# atmega328_breakout.net
KiCad netlist of a schematic drawn in EAGLE
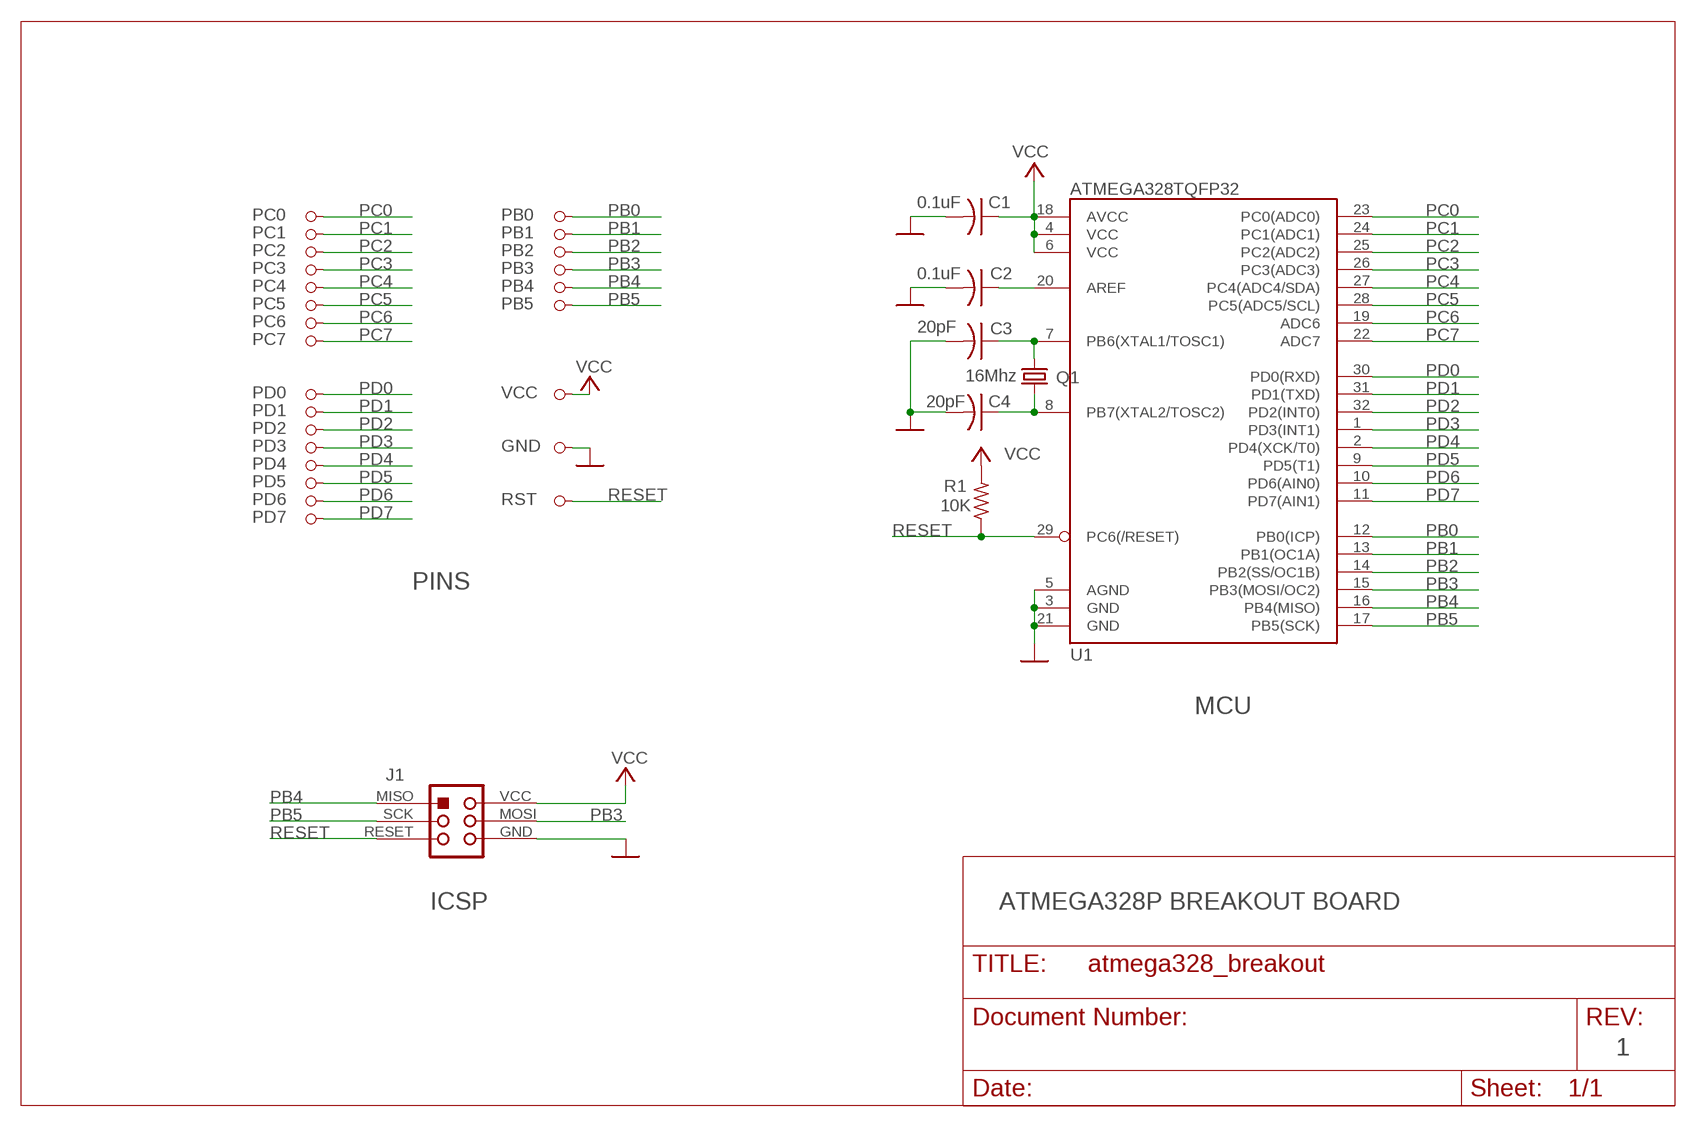
[diagram p0: schematic, sheet 1]

(export (version "E")
  (design (tool "Eeschema 10.0.6"))
  (components
    (comp (ref "C1")
      (value "0.1uF")
      (footprint "eagle-import:C0603")
      (libsource (lib "eagle-import") (part "CAP-C0603"))
    )
    (comp (ref "C2")
      (value "0.1uF")
      (footprint "eagle-import:C0603")
      (libsource (lib "eagle-import") (part "CAP-C0603"))
    )
    (comp (ref "C3")
      (value "20pF")
      (footprint "eagle-import:C0603")
      (libsource (lib "eagle-import") (part "CAP-C0603"))
    )
    (comp (ref "C4")
      (value "20pF")
      (footprint "eagle-import:C0603")
      (libsource (lib "eagle-import") (part "CAP-C0603"))
    )
    (comp (ref "GND")
      (value "PINHD-1X1")
      (footprint "eagle-import:1X01")
      (libsource (lib "eagle-import") (part "PINHD-1X1"))
    )
    (comp (ref "J1")
      (value "ICSP")
      (footprint "eagle-import:ICSP")
      (libsource (lib "eagle-import") (part "ICSP"))
    )
    (comp (ref "PB0")
      (value "PINHD-1X1")
      (footprint "eagle-import:1X01")
      (libsource (lib "eagle-import") (part "PINHD-1X1"))
    )
    (comp (ref "PB1")
      (value "PINHD-1X1")
      (footprint "eagle-import:1X01")
      (libsource (lib "eagle-import") (part "PINHD-1X1"))
    )
    (comp (ref "PB2")
      (value "PINHD-1X1")
      (footprint "eagle-import:1X01")
      (libsource (lib "eagle-import") (part "PINHD-1X1"))
    )
    (comp (ref "PB3")
      (value "PINHD-1X1")
      (footprint "eagle-import:1X01")
      (libsource (lib "eagle-import") (part "PINHD-1X1"))
    )
    (comp (ref "PB4")
      (value "PINHD-1X1")
      (footprint "eagle-import:1X01")
      (libsource (lib "eagle-import") (part "PINHD-1X1"))
    )
    (comp (ref "PB5")
      (value "PINHD-1X1")
      (footprint "eagle-import:1X01")
      (libsource (lib "eagle-import") (part "PINHD-1X1"))
    )
    (comp (ref "PC0")
      (value "PINHD-1X1")
      (footprint "eagle-import:1X01")
      (libsource (lib "eagle-import") (part "PINHD-1X1"))
    )
    (comp (ref "PC1")
      (value "PINHD-1X1")
      (footprint "eagle-import:1X01")
      (libsource (lib "eagle-import") (part "PINHD-1X1"))
    )
    (comp (ref "PC2")
      (value "PINHD-1X1")
      (footprint "eagle-import:1X01")
      (libsource (lib "eagle-import") (part "PINHD-1X1"))
    )
    (comp (ref "PC3")
      (value "PINHD-1X1")
      (footprint "eagle-import:1X01")
      (libsource (lib "eagle-import") (part "PINHD-1X1"))
    )
    (comp (ref "PC4")
      (value "PINHD-1X1")
      (footprint "eagle-import:1X01")
      (libsource (lib "eagle-import") (part "PINHD-1X1"))
    )
    (comp (ref "PC5")
      (value "PINHD-1X1")
      (footprint "eagle-import:1X01")
      (libsource (lib "eagle-import") (part "PINHD-1X1"))
    )
    (comp (ref "PC6")
      (value "PINHD-1X1")
      (footprint "eagle-import:1X01")
      (libsource (lib "eagle-import") (part "PINHD-1X1"))
    )
    (comp (ref "PC7")
      (value "PINHD-1X1")
      (footprint "eagle-import:1X01")
      (libsource (lib "eagle-import") (part "PINHD-1X1"))
    )
    (comp (ref "PD0")
      (value "PINHD-1X1")
      (footprint "eagle-import:1X01")
      (libsource (lib "eagle-import") (part "PINHD-1X1"))
    )
    (comp (ref "PD1")
      (value "PINHD-1X1")
      (footprint "eagle-import:1X01")
      (libsource (lib "eagle-import") (part "PINHD-1X1"))
    )
    (comp (ref "PD2")
      (value "PINHD-1X1")
      (footprint "eagle-import:1X01")
      (libsource (lib "eagle-import") (part "PINHD-1X1"))
    )
    (comp (ref "PD3")
      (value "PINHD-1X1")
      (footprint "eagle-import:1X01")
      (libsource (lib "eagle-import") (part "PINHD-1X1"))
    )
    (comp (ref "PD4")
      (value "PINHD-1X1")
      (footprint "eagle-import:1X01")
      (libsource (lib "eagle-import") (part "PINHD-1X1"))
    )
    (comp (ref "PD5")
      (value "PINHD-1X1")
      (footprint "eagle-import:1X01")
      (libsource (lib "eagle-import") (part "PINHD-1X1"))
    )
    (comp (ref "PD6")
      (value "PINHD-1X1")
      (footprint "eagle-import:1X01")
      (libsource (lib "eagle-import") (part "PINHD-1X1"))
    )
    (comp (ref "PD7")
      (value "PINHD-1X1")
      (footprint "eagle-import:1X01")
      (libsource (lib "eagle-import") (part "PINHD-1X1"))
    )
    (comp (ref "Q1")
      (value "16Mhz")
      (footprint "eagle-import:CRYSTAL-CTS406")
      (libsource (lib "eagle-import") (part "CRYSTALCTS406"))
    )
    (comp (ref "R1")
      (value "10K")
      (footprint "eagle-import:R0603")
      (libsource (lib "eagle-import") (part "RES-R0603"))
    )
    (comp (ref "RST")
      (value "PINHD-1X1")
      (footprint "eagle-import:1X01")
      (libsource (lib "eagle-import") (part "PINHD-1X1"))
    )
    (comp (ref "U1")
      (value "ATMEGA328TQFP32")
      (footprint "eagle-import:TQFP32-08")
      (libsource (lib "eagle-import") (part "ATMEGA328TQFP32"))
    )
    (comp (ref "VCC")
      (value "PINHD-1X1")
      (footprint "eagle-import:1X01")
      (libsource (lib "eagle-import") (part "PINHD-1X1"))
    )
  )
  (nets
    (net (code "1") (name "/PB0") (class "Default")
      (node (ref "PB0") (pin "1") (pinfunction "1_1") (pintype "passive"))
      (node (ref "U1") (pin "12") (pinfunction "PB0(ICP)_12") (pintype "bidirectional"))
    )
    (net (code "2") (name "/PB1") (class "Default")
      (node (ref "PB1") (pin "1") (pinfunction "1_1") (pintype "passive"))
      (node (ref "U1") (pin "13") (pinfunction "PB1(OC1A)_13") (pintype "bidirectional"))
    )
    (net (code "3") (name "/PB2") (class "Default")
      (node (ref "PB2") (pin "1") (pinfunction "1_1") (pintype "passive"))
      (node (ref "U1") (pin "14") (pinfunction "PB2(SS/OC1B)_14") (pintype "bidirectional"))
    )
    (net (code "4") (name "/PB3") (class "Default")
      (node (ref "J1") (pin "MOSI") (pinfunction "MOSI_MOSI") (pintype "passive"))
      (node (ref "PB3") (pin "1") (pinfunction "1_1") (pintype "passive"))
      (node (ref "U1") (pin "15") (pinfunction "PB3(MOSI/OC2)_15") (pintype "bidirectional"))
    )
    (net (code "5") (name "/PB4") (class "Default")
      (node (ref "J1") (pin "MISO") (pinfunction "MISO_MISO") (pintype "passive"))
      (node (ref "PB4") (pin "1") (pinfunction "1_1") (pintype "passive"))
      (node (ref "U1") (pin "16") (pinfunction "PB4(MISO)_16") (pintype "bidirectional"))
    )
    (net (code "6") (name "/PB5") (class "Default")
      (node (ref "J1") (pin "SCK") (pinfunction "SCK_SCK") (pintype "passive"))
      (node (ref "PB5") (pin "1") (pinfunction "1_1") (pintype "passive"))
      (node (ref "U1") (pin "17") (pinfunction "PB5(SCK)_17") (pintype "bidirectional"))
    )
    (net (code "7") (name "/PC0") (class "Default")
      (node (ref "PC0") (pin "1") (pinfunction "1_1") (pintype "passive"))
      (node (ref "U1") (pin "23") (pinfunction "PC0(ADC0)_23") (pintype "bidirectional"))
    )
    (net (code "8") (name "/PC1") (class "Default")
      (node (ref "PC1") (pin "1") (pinfunction "1_1") (pintype "passive"))
      (node (ref "U1") (pin "24") (pinfunction "PC1(ADC1)_24") (pintype "bidirectional"))
    )
    (net (code "9") (name "/PC2") (class "Default")
      (node (ref "PC2") (pin "1") (pinfunction "1_1") (pintype "passive"))
      (node (ref "U1") (pin "25") (pinfunction "PC2(ADC2)_25") (pintype "bidirectional"))
    )
    (net (code "10") (name "/PC3") (class "Default")
      (node (ref "PC3") (pin "1") (pinfunction "1_1") (pintype "passive"))
      (node (ref "U1") (pin "26") (pinfunction "PC3(ADC3)_26") (pintype "bidirectional"))
    )
    (net (code "11") (name "/PC4") (class "Default")
      (node (ref "PC4") (pin "1") (pinfunction "1_1") (pintype "passive"))
      (node (ref "U1") (pin "27") (pinfunction "PC4(ADC4/SDA)_27") (pintype "bidirectional"))
    )
    (net (code "12") (name "/PC5") (class "Default")
      (node (ref "PC5") (pin "1") (pinfunction "1_1") (pintype "passive"))
      (node (ref "U1") (pin "28") (pinfunction "PC5(ADC5/SCL)_28") (pintype "bidirectional"))
    )
    (net (code "13") (name "/PC6") (class "Default")
      (node (ref "PC6") (pin "1") (pinfunction "1_1") (pintype "passive"))
      (node (ref "U1") (pin "19") (pinfunction "ADC6_19") (pintype "bidirectional"))
    )
    (net (code "14") (name "/PC7") (class "Default")
      (node (ref "PC7") (pin "1") (pinfunction "1_1") (pintype "passive"))
      (node (ref "U1") (pin "22") (pinfunction "ADC7_22") (pintype "bidirectional"))
    )
    (net (code "15") (name "/PD0") (class "Default")
      (node (ref "PD0") (pin "1") (pinfunction "1_1") (pintype "passive"))
      (node (ref "U1") (pin "30") (pinfunction "PD0(RXD)_30") (pintype "bidirectional"))
    )
    (net (code "16") (name "/PD1") (class "Default")
      (node (ref "PD1") (pin "1") (pinfunction "1_1") (pintype "passive"))
      (node (ref "U1") (pin "31") (pinfunction "PD1(TXD)_31") (pintype "bidirectional"))
    )
    (net (code "17") (name "/PD2") (class "Default")
      (node (ref "PD2") (pin "1") (pinfunction "1_1") (pintype "passive"))
      (node (ref "U1") (pin "32") (pinfunction "PD2(INT0)_32") (pintype "bidirectional"))
    )
    (net (code "18") (name "/PD3") (class "Default")
      (node (ref "PD3") (pin "1") (pinfunction "1_1") (pintype "passive"))
      (node (ref "U1") (pin "1") (pinfunction "PD3(INT1)_1") (pintype "bidirectional"))
    )
    (net (code "19") (name "/PD4") (class "Default")
      (node (ref "PD4") (pin "1") (pinfunction "1_1") (pintype "passive"))
      (node (ref "U1") (pin "2") (pinfunction "PD4(XCK/T0)_2") (pintype "bidirectional"))
    )
    (net (code "20") (name "/PD5") (class "Default")
      (node (ref "PD5") (pin "1") (pinfunction "1_1") (pintype "passive"))
      (node (ref "U1") (pin "9") (pinfunction "PD5(T1)_9") (pintype "bidirectional"))
    )
    (net (code "21") (name "/PD6") (class "Default")
      (node (ref "PD6") (pin "1") (pinfunction "1_1") (pintype "passive"))
      (node (ref "U1") (pin "10") (pinfunction "PD6(AIN0)_10") (pintype "bidirectional"))
    )
    (net (code "22") (name "/PD7") (class "Default")
      (node (ref "PD7") (pin "1") (pinfunction "1_1") (pintype "passive"))
      (node (ref "U1") (pin "11") (pinfunction "PD7(AIN1)_11") (pintype "bidirectional"))
    )
    (net (code "23") (name "/RESET") (class "Default")
      (node (ref "J1") (pin "RESET") (pinfunction "RESET_RESET") (pintype "passive"))
      (node (ref "R1") (pin "1") (pinfunction "1_1") (pintype "passive"))
      (node (ref "RST") (pin "1") (pinfunction "1_1") (pintype "passive"))
      (node (ref "U1") (pin "29") (pinfunction "PC6(/RESET)_29") (pintype "bidirectional"))
    )
    (net (code "24") (name "GND") (class "Default")
      (node (ref "C1") (pin "2") (pinfunction "2_2") (pintype "passive"))
      (node (ref "C2") (pin "2") (pinfunction "2_2") (pintype "passive"))
      (node (ref "C3") (pin "2") (pinfunction "2_2") (pintype "passive"))
      (node (ref "C4") (pin "2") (pinfunction "2_2") (pintype "passive"))
      (node (ref "GND") (pin "1") (pinfunction "1_1") (pintype "passive"))
      (node (ref "J1") (pin "GND") (pinfunction "GND_GND") (pintype "power_in"))
      (node (ref "U1") (pin "21") (pinfunction "GND_21") (pintype "power_in"))
      (node (ref "U1") (pin "3") (pinfunction "GND_3") (pintype "power_in"))
      (node (ref "U1") (pin "5") (pinfunction "AGND_5") (pintype "power_in"))
    )
    (net (code "25") (name "Net-(Q1-2)") (class "Default")
      (node (ref "C4") (pin "1") (pinfunction "1_1") (pintype "passive"))
      (node (ref "Q1") (pin "3") (pinfunction "2_3") (pintype "passive"))
      (node (ref "U1") (pin "8") (pinfunction "PB7(XTAL2/TOSC2)_8") (pintype "bidirectional"))
    )
    (net (code "26") (name "Net-(U1-AREF)") (class "Default")
      (node (ref "C2") (pin "1") (pinfunction "1_1") (pintype "passive"))
      (node (ref "U1") (pin "20") (pinfunction "AREF_20") (pintype "power_in"))
    )
    (net (code "27") (name "Net-(U1-PB6(XTAL1{slash}TOSC1))") (class "Default")
      (node (ref "C3") (pin "1") (pinfunction "1_1") (pintype "passive"))
      (node (ref "Q1") (pin "1") (pinfunction "1_1") (pintype "passive"))
      (node (ref "U1") (pin "7") (pinfunction "PB6(XTAL1/TOSC1)_7") (pintype "bidirectional"))
    )
    (net (code "28") (name "VCC") (class "Default")
      (node (ref "C1") (pin "1") (pinfunction "1_1") (pintype "passive"))
      (node (ref "J1") (pin "VCC") (pinfunction "VCC_VCC") (pintype "power_in"))
      (node (ref "R1") (pin "2") (pinfunction "2_2") (pintype "passive"))
      (node (ref "U1") (pin "18") (pinfunction "AVCC_18") (pintype "power_in"))
      (node (ref "U1") (pin "4") (pinfunction "VCC_4") (pintype "power_in"))
      (node (ref "U1") (pin "6") (pinfunction "VCC_6") (pintype "power_in"))
      (node (ref "VCC") (pin "1") (pinfunction "1_1") (pintype "passive"))
    )
  )
)
